# plaquinha.net
KiCad netlist of a schematic drawn in EAGLE
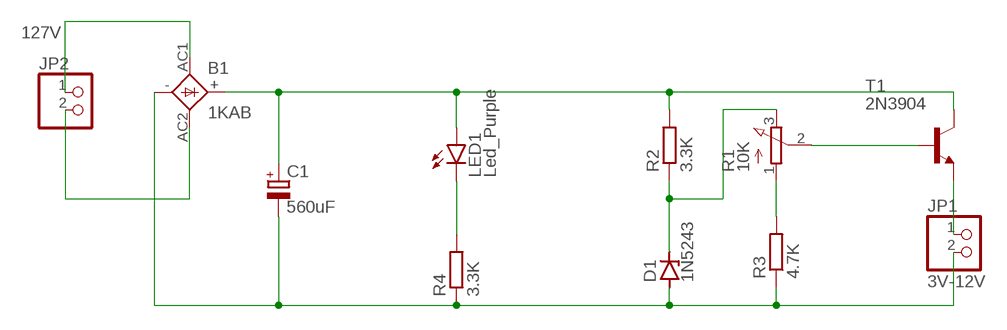
[diagram p0: schematic, sheet 1]

(export (version "E")
  (design (tool "Eeschema 10.0.6"))
  (components
    (comp (ref "B1")
      (value "1KAB")
      (footprint "eagle-import:1KAB")
      (libsource (lib "eagle-import") (part "1KAB"))
    )
    (comp (ref "C1")
      (value "560uF")
      (footprint "eagle-import:E5-10,5")
      (libsource (lib "eagle-import") (part "CPOL-EUE5-10.5"))
    )
    (comp (ref "D1")
      (value "1N5243")
      (footprint "eagle-import:DO41Z10")
      (libsource (lib "eagle-import") (part "1N4728"))
    )
    (comp (ref "JP1")
      (value "3V-12V")
      (footprint "eagle-import:1X02")
      (libsource (lib "eagle-import") (part "PINHD-1X2"))
    )
    (comp (ref "JP2")
      (value "127V")
      (footprint "eagle-import:1X02")
      (libsource (lib "eagle-import") (part "PINHD-1X2"))
    )
    (comp (ref "LED1")
      (value "Led_Purple")
      (footprint "eagle-import:LED5MM")
      (libsource (lib "eagle-import") (part "LED5MM"))
    )
    (comp (ref "R1")
      (value "10K")
      (footprint "eagle-import:3RP_1610N")
      (libsource (lib "eagle-import") (part "3RP/1610N"))
    )
    (comp (ref "R2")
      (value "3.3K")
      (footprint "eagle-import:0204_7")
      (libsource (lib "eagle-import") (part "R-EU_0204/7"))
    )
    (comp (ref "R3")
      (value "4.7K")
      (footprint "eagle-import:0204_7")
      (libsource (lib "eagle-import") (part "R-EU_0204/7"))
    )
    (comp (ref "R4")
      (value "3.3K")
      (footprint "eagle-import:0204_7")
      (libsource (lib "eagle-import") (part "R-EU_0204/7"))
    )
    (comp (ref "T1")
      (value "2N3904")
      (footprint "eagle-import:TO92")
      (libsource (lib "eagle-import") (part "2N3904"))
    )
  )
  (nets
    (net (code "1") (name "Net-(B1-Pad-)") (class "Default")
      (node (ref "B1") (pin "-") (pinfunction "-_-") (pintype "passive"))
      (node (ref "C1") (pin "-") (pinfunction "-_-") (pintype "passive"))
      (node (ref "D1") (pin "A") (pinfunction "A_A") (pintype "passive"))
      (node (ref "JP1") (pin "2") (pinfunction "2_2") (pintype "passive"))
      (node (ref "R3") (pin "1") (pinfunction "1_1") (pintype "passive"))
      (node (ref "R4") (pin "1") (pinfunction "1_1") (pintype "passive"))
    )
    (net (code "2") (name "Net-(B1-PadAC1)") (class "Default")
      (node (ref "B1") (pin "AC1") (pinfunction "AC1_AC1") (pintype "passive"))
      (node (ref "JP2") (pin "1") (pinfunction "1_1") (pintype "passive"))
    )
    (net (code "3") (name "Net-(B1-PadAC2)") (class "Default")
      (node (ref "B1") (pin "AC2") (pinfunction "AC2_AC2") (pintype "passive"))
      (node (ref "JP2") (pin "2") (pinfunction "2_2") (pintype "passive"))
    )
    (net (code "4") (name "Net-(LED1-C)") (class "Default")
      (node (ref "LED1") (pin "K") (pinfunction "C_K") (pintype "passive"))
      (node (ref "R4") (pin "2") (pinfunction "2_2") (pintype "passive"))
    )
    (net (code "5") (name "Net-(R1-A)") (class "Default")
      (node (ref "R1") (pin "1") (pinfunction "A_1") (pintype "passive"))
      (node (ref "R3") (pin "2") (pinfunction "2_2") (pintype "passive"))
    )
    (net (code "6") (name "Net-(R1-E)") (class "Default")
      (node (ref "D1") (pin "C") (pinfunction "C_C") (pintype "passive"))
      (node (ref "R1") (pin "3") (pinfunction "E_3") (pintype "passive"))
      (node (ref "R2") (pin "1") (pinfunction "1_1") (pintype "passive"))
    )
    (net (code "7") (name "Net-(R1-S)") (class "Default")
      (node (ref "R1") (pin "2") (pinfunction "S_2") (pintype "passive"))
      (node (ref "T1") (pin "2") (pinfunction "B_2") (pintype "passive"))
    )
    (net (code "8") (name "Net-(T1-C)") (class "Default")
      (node (ref "B1") (pin "+") (pinfunction "+_+") (pintype "passive"))
      (node (ref "C1") (pin "+") (pinfunction "+_+") (pintype "passive"))
      (node (ref "LED1") (pin "A") (pinfunction "A_A") (pintype "passive"))
      (node (ref "R2") (pin "2") (pinfunction "2_2") (pintype "passive"))
      (node (ref "T1") (pin "1") (pinfunction "C_1") (pintype "passive"))
    )
    (net (code "9") (name "Net-(T1-E)") (class "Default")
      (node (ref "JP1") (pin "1") (pinfunction "1_1") (pintype "passive"))
      (node (ref "T1") (pin "3") (pinfunction "E_3") (pintype "passive"))
    )
  )
)
